# raspi-shield.net
KiCad netlist of a schematic drawn in EAGLE
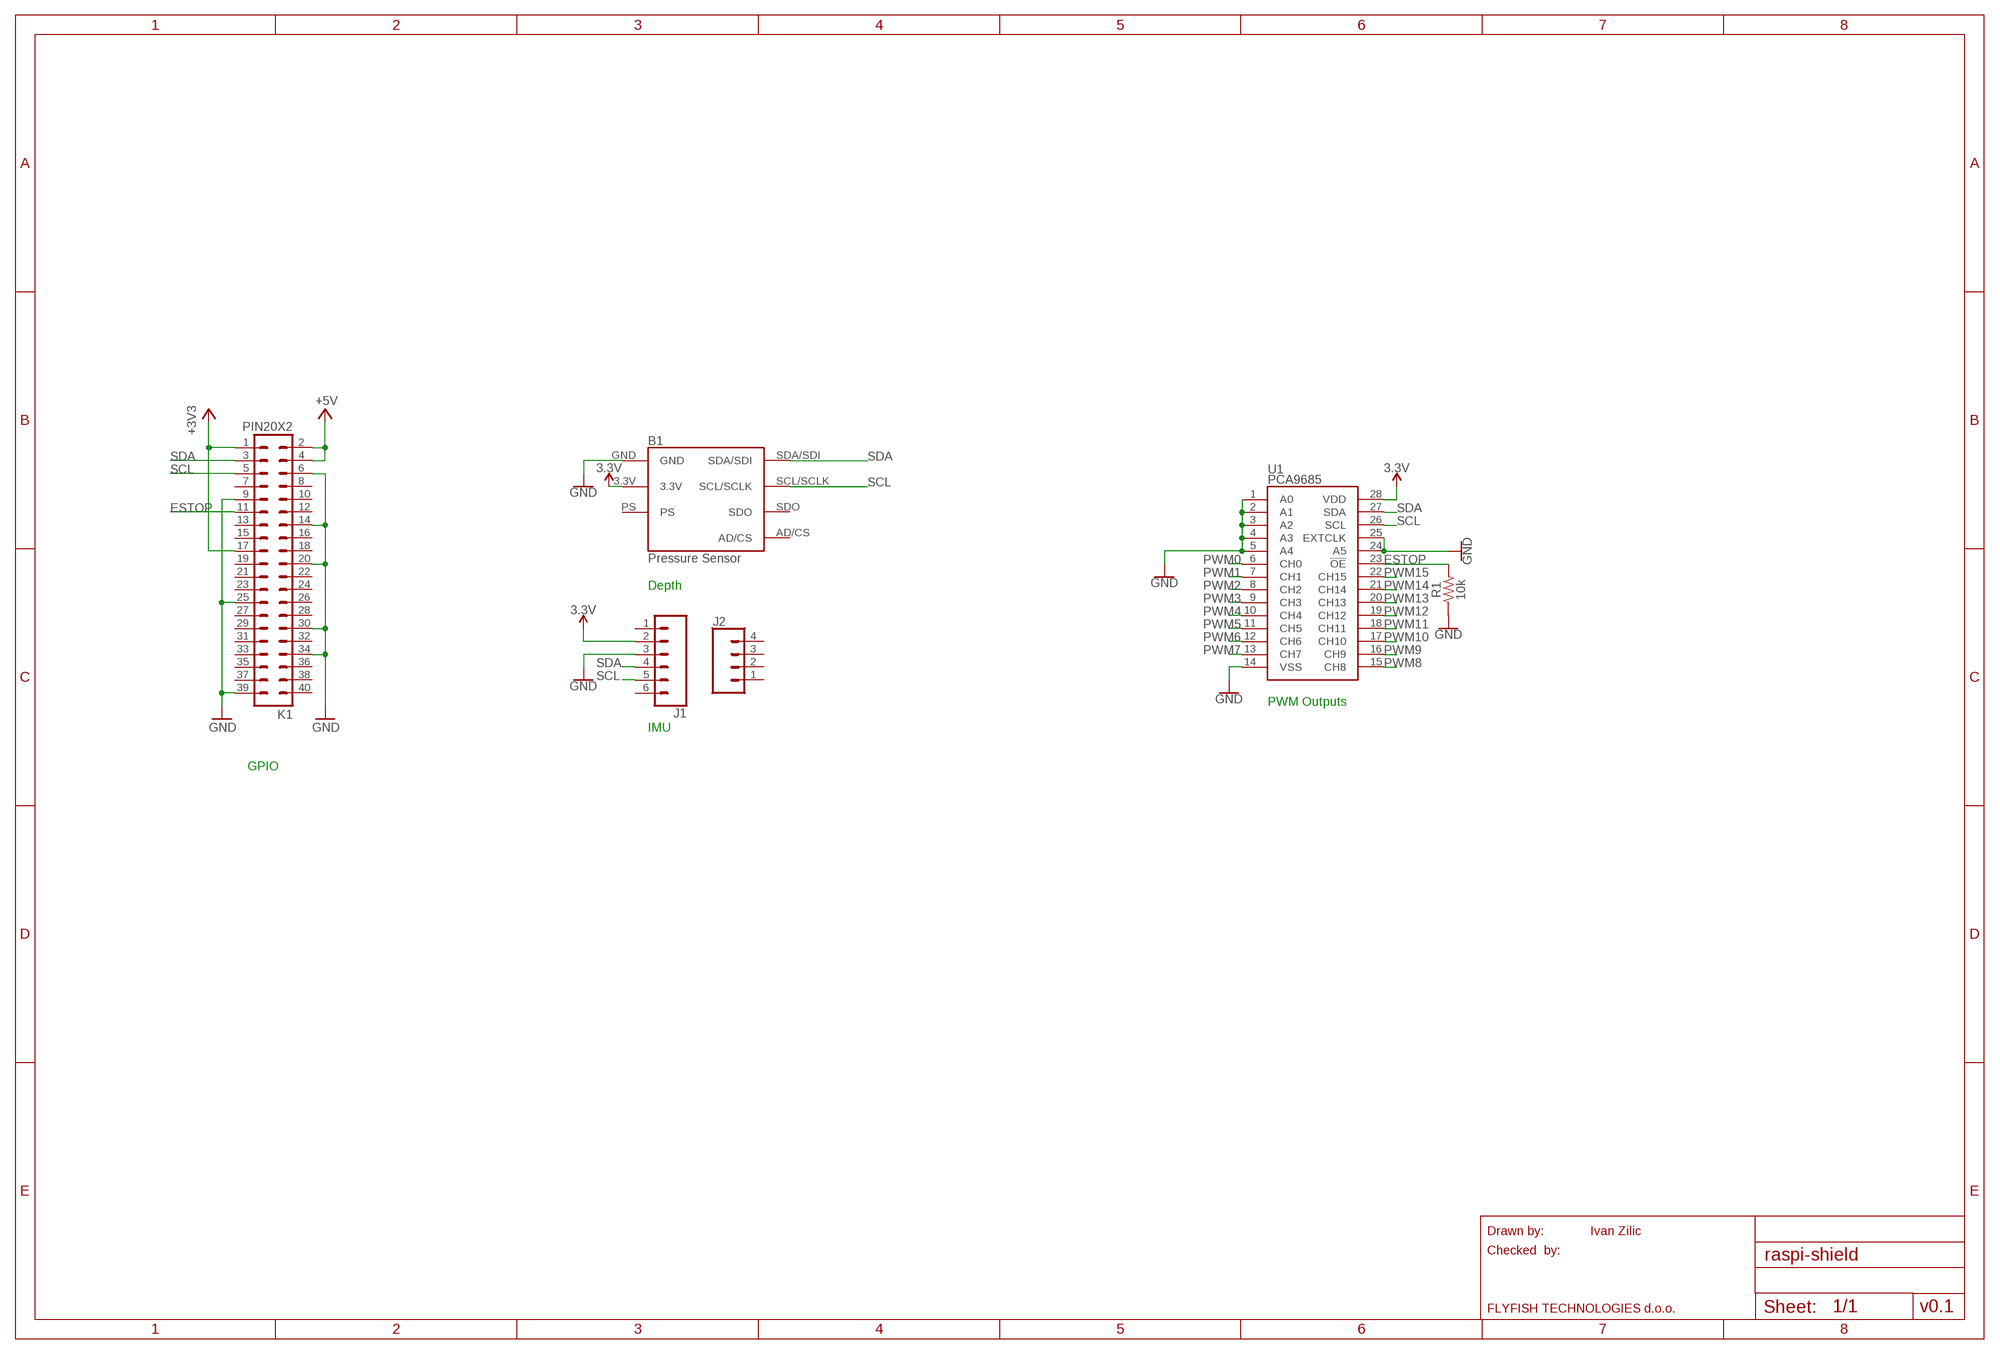
[diagram p0: schematic, sheet 1]

(export (version "E")
  (design (tool "Eeschema 10.0.6"))
  (components
    (comp (ref "B1")
      (value "Pressure Sensor")
      (footprint "eagle-import:SPARKFUN_MS5803-14BA_BREAKOUT")
      (libsource (lib "eagle-import") (part "SPARKFUN_MS5803-14BA_BREAKOUT"))
    )
    (comp (ref "J1")
      (value "CONN_06NO_SILK_FEMALE_PTH")
      (footprint "eagle-import:1X06_NO_SILK")
      (libsource (lib "eagle-import") (part "CONN_06NO_SILK_FEMALE_PTH"))
    )
    (comp (ref "J2")
      (value "CONN_041X04_NO_SILK")
      (footprint "eagle-import:1X04_NO_SILK")
      (libsource (lib "eagle-import") (part "CONN_041X04_NO_SILK"))
    )
    (comp (ref "K1")
      (value "PIN20X2")
      (footprint "eagle-import:PIN_20X2")
      (libsource (lib "eagle-import") (part "PIN20X2"))
    )
    (comp (ref "R1")
      (value "10k")
      (footprint "eagle-import:0603")
      (libsource (lib "eagle-import") (part "10KOHM-0603-1/10W-1%"))
    )
    (comp (ref "U1")
      (value "PCA9685")
      (footprint "eagle-import:TSSOP-28_4MM")
      (libsource (lib "eagle-import") (part "PCA9685"))
    )
  )
  (nets
    (net (code "1") (name "+3V3") (class "Default")
      (node (ref "K1") (pin "1") (pinfunction "1_1") (pintype "passive"))
      (node (ref "K1") (pin "17") (pinfunction "17_17") (pintype "passive"))
    )
    (net (code "2") (name "+5V") (class "Default")
      (node (ref "K1") (pin "2") (pinfunction "2_2") (pintype "passive"))
      (node (ref "K1") (pin "4") (pinfunction "4_4") (pintype "passive"))
    )
    (net (code "3") (name "/ESTOP") (class "Default")
      (node (ref "K1") (pin "11") (pinfunction "11_11") (pintype "passive"))
      (node (ref "R1") (pin "2") (pinfunction "2_2") (pintype "passive"))
      (node (ref "U1") (pin "23") (pinfunction "~{OE}_23") (pintype "bidirectional"))
    )
    (net (code "4") (name "/PWM0") (class "Default")
      (node (ref "U1") (pin "6") (pinfunction "CH0_6") (pintype "bidirectional"))
    )
    (net (code "5") (name "/PWM1") (class "Default")
      (node (ref "U1") (pin "7") (pinfunction "CH1_7") (pintype "bidirectional"))
    )
    (net (code "6") (name "/PWM2") (class "Default")
      (node (ref "U1") (pin "8") (pinfunction "CH2_8") (pintype "bidirectional"))
    )
    (net (code "7") (name "/PWM3") (class "Default")
      (node (ref "U1") (pin "9") (pinfunction "CH3_9") (pintype "bidirectional"))
    )
    (net (code "8") (name "/PWM4") (class "Default")
      (node (ref "U1") (pin "10") (pinfunction "CH4_10") (pintype "bidirectional"))
    )
    (net (code "9") (name "/PWM5") (class "Default")
      (node (ref "U1") (pin "11") (pinfunction "CH5_11") (pintype "bidirectional"))
    )
    (net (code "10") (name "/PWM6") (class "Default")
      (node (ref "U1") (pin "12") (pinfunction "CH6_12") (pintype "bidirectional"))
    )
    (net (code "11") (name "/PWM7") (class "Default")
      (node (ref "U1") (pin "13") (pinfunction "CH7_13") (pintype "bidirectional"))
    )
    (net (code "12") (name "/PWM8") (class "Default")
      (node (ref "U1") (pin "15") (pinfunction "CH8_15") (pintype "bidirectional"))
    )
    (net (code "13") (name "/PWM9") (class "Default")
      (node (ref "U1") (pin "16") (pinfunction "CH9_16") (pintype "bidirectional"))
    )
    (net (code "14") (name "/PWM10") (class "Default")
      (node (ref "U1") (pin "17") (pinfunction "CH10_17") (pintype "bidirectional"))
    )
    (net (code "15") (name "/PWM11") (class "Default")
      (node (ref "U1") (pin "18") (pinfunction "CH11_18") (pintype "bidirectional"))
    )
    (net (code "16") (name "/PWM12") (class "Default")
      (node (ref "U1") (pin "19") (pinfunction "CH12_19") (pintype "bidirectional"))
    )
    (net (code "17") (name "/PWM13") (class "Default")
      (node (ref "U1") (pin "20") (pinfunction "CH13_20") (pintype "bidirectional"))
    )
    (net (code "18") (name "/PWM14") (class "Default")
      (node (ref "U1") (pin "21") (pinfunction "CH14_21") (pintype "bidirectional"))
    )
    (net (code "19") (name "/PWM15") (class "Default")
      (node (ref "U1") (pin "22") (pinfunction "CH15_22") (pintype "bidirectional"))
    )
    (net (code "20") (name "/SCL") (class "Default")
      (node (ref "B1") (pin "SCL/SCLK") (pinfunction "SCL/SCLK_SCL/SCLK") (pintype "bidirectional"))
      (node (ref "J1") (pin "5") (pinfunction "5_5") (pintype "passive"))
      (node (ref "K1") (pin "5") (pinfunction "5_5") (pintype "passive"))
      (node (ref "U1") (pin "26") (pinfunction "SCL_26") (pintype "bidirectional"))
    )
    (net (code "21") (name "/SDA") (class "Default")
      (node (ref "B1") (pin "SDA/SDI") (pinfunction "SDA/SDI_SDA/SDI") (pintype "bidirectional"))
      (node (ref "J1") (pin "4") (pinfunction "4_4") (pintype "passive"))
      (node (ref "K1") (pin "3") (pinfunction "3_3") (pintype "passive"))
      (node (ref "U1") (pin "27") (pinfunction "SDA_27") (pintype "bidirectional"))
    )
    (net (code "22") (name "3.3V") (class "Default")
      (node (ref "B1") (pin "3.3V") (pinfunction "3.3V_3.3V") (pintype "bidirectional"))
      (node (ref "J1") (pin "2") (pinfunction "2_2") (pintype "passive"))
      (node (ref "U1") (pin "28") (pinfunction "VDD_28") (pintype "bidirectional"))
    )
    (net (code "23") (name "GND") (class "Default")
      (node (ref "B1") (pin "GND") (pinfunction "GND_GND") (pintype "bidirectional"))
      (node (ref "J1") (pin "3") (pinfunction "3_3") (pintype "passive"))
      (node (ref "K1") (pin "14") (pinfunction "14_14") (pintype "passive"))
      (node (ref "K1") (pin "20") (pinfunction "20_20") (pintype "passive"))
      (node (ref "K1") (pin "25") (pinfunction "25_25") (pintype "passive"))
      (node (ref "K1") (pin "30") (pinfunction "30_30") (pintype "passive"))
      (node (ref "K1") (pin "34") (pinfunction "34_34") (pintype "passive"))
      (node (ref "K1") (pin "39") (pinfunction "39_39") (pintype "passive"))
      (node (ref "K1") (pin "6") (pinfunction "6_6") (pintype "passive"))
      (node (ref "K1") (pin "9") (pinfunction "9_9") (pintype "passive"))
      (node (ref "R1") (pin "1") (pinfunction "1_1") (pintype "passive"))
      (node (ref "U1") (pin "1") (pinfunction "A0_1") (pintype "bidirectional"))
      (node (ref "U1") (pin "14") (pinfunction "VSS_14") (pintype "bidirectional"))
      (node (ref "U1") (pin "2") (pinfunction "A1_2") (pintype "bidirectional"))
      (node (ref "U1") (pin "24") (pinfunction "A5_24") (pintype "bidirectional"))
      (node (ref "U1") (pin "25") (pinfunction "EXTCLK_25") (pintype "bidirectional"))
      (node (ref "U1") (pin "3") (pinfunction "A2_3") (pintype "bidirectional"))
      (node (ref "U1") (pin "4") (pinfunction "A3_4") (pintype "bidirectional"))
      (node (ref "U1") (pin "5") (pinfunction "A4_5") (pintype "bidirectional"))
    )
    (net (code "24") (name "unconnected-(B1-PadAD{slash}CS)") (class "Default")
      (node (ref "B1") (pin "AD/CS") (pinfunction "AD/CS_AD/CS") (pintype "bidirectional"))
    )
    (net (code "25") (name "unconnected-(B1-PadPS)") (class "Default")
      (node (ref "B1") (pin "PS") (pinfunction "PS_PS") (pintype "bidirectional"))
    )
    (net (code "26") (name "unconnected-(B1-PadSDO)") (class "Default")
      (node (ref "B1") (pin "SDO") (pinfunction "SDO_SDO") (pintype "bidirectional"))
    )
    (net (code "27") (name "unconnected-(J1-Pad1)") (class "Default")
      (node (ref "J1") (pin "1") (pinfunction "1_1") (pintype "passive"))
    )
    (net (code "28") (name "unconnected-(J1-Pad6)") (class "Default")
      (node (ref "J1") (pin "6") (pinfunction "6_6") (pintype "passive"))
    )
    (net (code "29") (name "unconnected-(J2-Pad1)") (class "Default")
      (node (ref "J2") (pin "1") (pinfunction "1_1") (pintype "passive"))
    )
    (net (code "30") (name "unconnected-(J2-Pad2)") (class "Default")
      (node (ref "J2") (pin "2") (pinfunction "2_2") (pintype "passive"))
    )
    (net (code "31") (name "unconnected-(J2-Pad3)") (class "Default")
      (node (ref "J2") (pin "3") (pinfunction "3_3") (pintype "passive"))
    )
    (net (code "32") (name "unconnected-(J2-Pad4)") (class "Default")
      (node (ref "J2") (pin "4") (pinfunction "4_4") (pintype "passive"))
    )
    (net (code "33") (name "unconnected-(K1-Pad7)") (class "Default")
      (node (ref "K1") (pin "7") (pinfunction "7_7") (pintype "passive"))
    )
    (net (code "34") (name "unconnected-(K1-Pad8)") (class "Default")
      (node (ref "K1") (pin "8") (pinfunction "8_8") (pintype "passive"))
    )
    (net (code "35") (name "unconnected-(K1-Pad10)") (class "Default")
      (node (ref "K1") (pin "10") (pinfunction "10_10") (pintype "passive"))
    )
    (net (code "36") (name "unconnected-(K1-Pad12)") (class "Default")
      (node (ref "K1") (pin "12") (pinfunction "12_12") (pintype "passive"))
    )
    (net (code "37") (name "unconnected-(K1-Pad13)") (class "Default")
      (node (ref "K1") (pin "13") (pinfunction "13_13") (pintype "passive"))
    )
    (net (code "38") (name "unconnected-(K1-Pad15)") (class "Default")
      (node (ref "K1") (pin "15") (pinfunction "15_15") (pintype "passive"))
    )
    (net (code "39") (name "unconnected-(K1-Pad16)") (class "Default")
      (node (ref "K1") (pin "16") (pinfunction "16_16") (pintype "passive"))
    )
    (net (code "40") (name "unconnected-(K1-Pad18)") (class "Default")
      (node (ref "K1") (pin "18") (pinfunction "18_18") (pintype "passive"))
    )
    (net (code "41") (name "unconnected-(K1-Pad19)") (class "Default")
      (node (ref "K1") (pin "19") (pinfunction "19_19") (pintype "passive"))
    )
    (net (code "42") (name "unconnected-(K1-Pad21)") (class "Default")
      (node (ref "K1") (pin "21") (pinfunction "21_21") (pintype "passive"))
    )
    (net (code "43") (name "unconnected-(K1-Pad22)") (class "Default")
      (node (ref "K1") (pin "22") (pinfunction "22_22") (pintype "passive"))
    )
    (net (code "44") (name "unconnected-(K1-Pad23)") (class "Default")
      (node (ref "K1") (pin "23") (pinfunction "23_23") (pintype "passive"))
    )
    (net (code "45") (name "unconnected-(K1-Pad24)") (class "Default")
      (node (ref "K1") (pin "24") (pinfunction "24_24") (pintype "passive"))
    )
    (net (code "46") (name "unconnected-(K1-Pad26)") (class "Default")
      (node (ref "K1") (pin "26") (pinfunction "26_26") (pintype "passive"))
    )
    (net (code "47") (name "unconnected-(K1-Pad27)") (class "Default")
      (node (ref "K1") (pin "27") (pinfunction "27_27") (pintype "passive"))
    )
    (net (code "48") (name "unconnected-(K1-Pad28)") (class "Default")
      (node (ref "K1") (pin "28") (pinfunction "28_28") (pintype "passive"))
    )
    (net (code "49") (name "unconnected-(K1-Pad29)") (class "Default")
      (node (ref "K1") (pin "29") (pinfunction "29_29") (pintype "passive"))
    )
    (net (code "50") (name "unconnected-(K1-Pad31)") (class "Default")
      (node (ref "K1") (pin "31") (pinfunction "31_31") (pintype "passive"))
    )
    (net (code "51") (name "unconnected-(K1-Pad32)") (class "Default")
      (node (ref "K1") (pin "32") (pinfunction "32_32") (pintype "passive"))
    )
    (net (code "52") (name "unconnected-(K1-Pad33)") (class "Default")
      (node (ref "K1") (pin "33") (pinfunction "33_33") (pintype "passive"))
    )
    (net (code "53") (name "unconnected-(K1-Pad35)") (class "Default")
      (node (ref "K1") (pin "35") (pinfunction "35_35") (pintype "passive"))
    )
    (net (code "54") (name "unconnected-(K1-Pad36)") (class "Default")
      (node (ref "K1") (pin "36") (pinfunction "36_36") (pintype "passive"))
    )
    (net (code "55") (name "unconnected-(K1-Pad37)") (class "Default")
      (node (ref "K1") (pin "37") (pinfunction "37_37") (pintype "passive"))
    )
    (net (code "56") (name "unconnected-(K1-Pad38)") (class "Default")
      (node (ref "K1") (pin "38") (pinfunction "38_38") (pintype "passive"))
    )
    (net (code "57") (name "unconnected-(K1-Pad40)") (class "Default")
      (node (ref "K1") (pin "40") (pinfunction "40_40") (pintype "passive"))
    )
  )
)
